# MDU_base.net
KiCad netlist of a schematic drawn in EAGLE
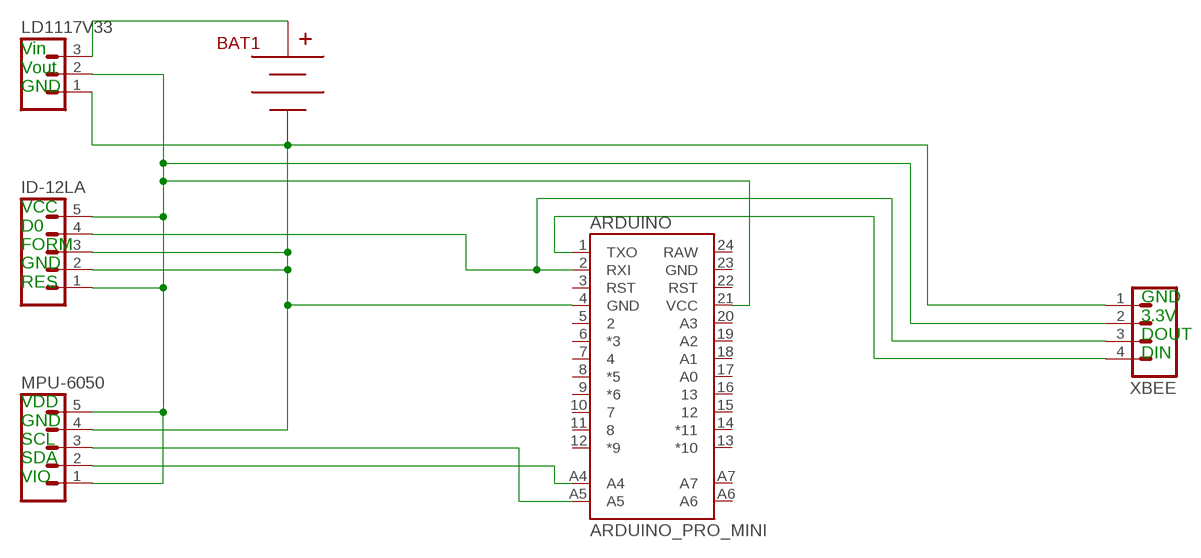
[diagram p0: schematic, sheet 1]

(export (version "E")
  (design (tool "Eeschema 10.0.6"))
  (components
    (comp (ref "ARDUINO")
      (value "ARDUINO_PRO_MINI")
      (footprint "eagle-import:ARDUINO_PRO_MINI")
      (libsource (lib "eagle-import") (part "ARDUINO_PRO_MINI"))
    )
    (comp (ref "BAT1")
      (value "BC9VPC")
      (footprint "eagle-import:BC9VPC")
      (libsource (lib "eagle-import") (part "BC9VPC"))
    )
    (comp (ref "ID-12LA")
      (value "M05NO_SILK")
      (footprint "eagle-import:1X05_NO_SILK")
      (libsource (lib "eagle-import") (part "M05NO_SILK"))
    )
    (comp (ref "LD1117V33")
      (value "M031X03_NO_SILK")
      (footprint "eagle-import:1X03_NO_SILK")
      (libsource (lib "eagle-import") (part "M031X03_NO_SILK"))
    )
    (comp (ref "MPU-6050")
      (value "M05NO_SILK")
      (footprint "eagle-import:1X05_NO_SILK")
      (libsource (lib "eagle-import") (part "M05NO_SILK"))
    )
    (comp (ref "XBEE")
      (value "M041X04_NO_SILK")
      (footprint "eagle-import:1X04_NO_SILK")
      (libsource (lib "eagle-import") (part "M041X04_NO_SILK"))
    )
  )
  (nets
    (net (code "1") (name "Net-(ARDUINO-GND-Pad4)") (class "Default")
      (node (ref "ARDUINO") (pin "4") (pinfunction "GND_4") (pintype "bidirectional"))
      (node (ref "BAT1") (pin "V-") (pinfunction "V-_V-") (pintype "bidirectional"))
      (node (ref "ID-12LA") (pin "2") (pinfunction "2_2") (pintype "passive"))
      (node (ref "ID-12LA") (pin "3") (pinfunction "3_3") (pintype "passive"))
      (node (ref "LD1117V33") (pin "1") (pinfunction "1_1") (pintype "passive"))
      (node (ref "MPU-6050") (pin "4") (pinfunction "4_4") (pintype "passive"))
      (node (ref "XBEE") (pin "1") (pinfunction "1_1") (pintype "passive"))
    )
    (net (code "2") (name "Net-(ARDUINO-PadA4)") (class "Default")
      (node (ref "ARDUINO") (pin "A4") (pinfunction "A4_A4") (pintype "bidirectional"))
      (node (ref "MPU-6050") (pin "2") (pinfunction "2_2") (pintype "passive"))
    )
    (net (code "3") (name "Net-(ARDUINO-PadA5)") (class "Default")
      (node (ref "ARDUINO") (pin "A5") (pinfunction "A5_A5") (pintype "bidirectional"))
      (node (ref "MPU-6050") (pin "3") (pinfunction "3_3") (pintype "passive"))
    )
    (net (code "4") (name "Net-(ARDUINO-RXI)") (class "Default")
      (node (ref "ARDUINO") (pin "2") (pinfunction "RXI_2") (pintype "bidirectional"))
      (node (ref "ID-12LA") (pin "4") (pinfunction "4_4") (pintype "passive"))
      (node (ref "XBEE") (pin "3") (pinfunction "3_3") (pintype "passive"))
    )
    (net (code "5") (name "Net-(ARDUINO-TXO)") (class "Default")
      (node (ref "ARDUINO") (pin "1") (pinfunction "TXO_1") (pintype "bidirectional"))
      (node (ref "XBEE") (pin "4") (pinfunction "4_4") (pintype "passive"))
    )
    (net (code "6") (name "Net-(ARDUINO-VCC)") (class "Default")
      (node (ref "ARDUINO") (pin "21") (pinfunction "VCC_21") (pintype "bidirectional"))
      (node (ref "ID-12LA") (pin "1") (pinfunction "1_1") (pintype "passive"))
      (node (ref "ID-12LA") (pin "5") (pinfunction "5_5") (pintype "passive"))
      (node (ref "LD1117V33") (pin "2") (pinfunction "2_2") (pintype "passive"))
      (node (ref "MPU-6050") (pin "1") (pinfunction "1_1") (pintype "passive"))
      (node (ref "MPU-6050") (pin "5") (pinfunction "5_5") (pintype "passive"))
      (node (ref "XBEE") (pin "2") (pinfunction "2_2") (pintype "passive"))
    )
    (net (code "7") (name "Net-(BAT1-PadV+)") (class "Default")
      (node (ref "BAT1") (pin "V+") (pinfunction "V+_V+") (pintype "bidirectional"))
      (node (ref "LD1117V33") (pin "3") (pinfunction "3_3") (pintype "passive"))
    )
    (net (code "8") (name "unconnected-(ARDUINO-*3-Pad6)") (class "Default")
      (node (ref "ARDUINO") (pin "6") (pinfunction "*3_6") (pintype "bidirectional"))
    )
    (net (code "9") (name "unconnected-(ARDUINO-*5-Pad8)") (class "Default")
      (node (ref "ARDUINO") (pin "8") (pinfunction "*5_8") (pintype "bidirectional"))
    )
    (net (code "10") (name "unconnected-(ARDUINO-*6-Pad9)") (class "Default")
      (node (ref "ARDUINO") (pin "9") (pinfunction "*6_9") (pintype "bidirectional"))
    )
    (net (code "11") (name "unconnected-(ARDUINO-*9-Pad12)") (class "Default")
      (node (ref "ARDUINO") (pin "12") (pinfunction "*9_12") (pintype "bidirectional"))
    )
    (net (code "12") (name "unconnected-(ARDUINO-*10-Pad13)") (class "Default")
      (node (ref "ARDUINO") (pin "13") (pinfunction "*10_13") (pintype "bidirectional"))
    )
    (net (code "13") (name "unconnected-(ARDUINO-*11-Pad14)") (class "Default")
      (node (ref "ARDUINO") (pin "14") (pinfunction "*11_14") (pintype "bidirectional"))
    )
    (net (code "14") (name "unconnected-(ARDUINO-2-Pad5)") (class "Default")
      (node (ref "ARDUINO") (pin "5") (pinfunction "2_5") (pintype "bidirectional"))
    )
    (net (code "15") (name "unconnected-(ARDUINO-4-Pad7)") (class "Default")
      (node (ref "ARDUINO") (pin "7") (pinfunction "4_7") (pintype "bidirectional"))
    )
    (net (code "16") (name "unconnected-(ARDUINO-7-Pad10)") (class "Default")
      (node (ref "ARDUINO") (pin "10") (pinfunction "7_10") (pintype "bidirectional"))
    )
    (net (code "17") (name "unconnected-(ARDUINO-8-Pad11)") (class "Default")
      (node (ref "ARDUINO") (pin "11") (pinfunction "8_11") (pintype "bidirectional"))
    )
    (net (code "18") (name "unconnected-(ARDUINO-12-Pad15)") (class "Default")
      (node (ref "ARDUINO") (pin "15") (pinfunction "12_15") (pintype "bidirectional"))
    )
    (net (code "19") (name "unconnected-(ARDUINO-13-Pad16)") (class "Default")
      (node (ref "ARDUINO") (pin "16") (pinfunction "13_16") (pintype "bidirectional"))
    )
    (net (code "20") (name "unconnected-(ARDUINO-A0-Pad17)") (class "Default")
      (node (ref "ARDUINO") (pin "17") (pinfunction "A0_17") (pintype "bidirectional"))
    )
    (net (code "21") (name "unconnected-(ARDUINO-A1-Pad18)") (class "Default")
      (node (ref "ARDUINO") (pin "18") (pinfunction "A1_18") (pintype "bidirectional"))
    )
    (net (code "22") (name "unconnected-(ARDUINO-A2-Pad19)") (class "Default")
      (node (ref "ARDUINO") (pin "19") (pinfunction "A2_19") (pintype "bidirectional"))
    )
    (net (code "23") (name "unconnected-(ARDUINO-A3-Pad20)") (class "Default")
      (node (ref "ARDUINO") (pin "20") (pinfunction "A3_20") (pintype "bidirectional"))
    )
    (net (code "24") (name "unconnected-(ARDUINO-GND-Pad23)") (class "Default")
      (node (ref "ARDUINO") (pin "23") (pinfunction "GND_23") (pintype "bidirectional"))
    )
    (net (code "25") (name "unconnected-(ARDUINO-PadA6)") (class "Default")
      (node (ref "ARDUINO") (pin "A6") (pinfunction "A6_A6") (pintype "bidirectional"))
    )
    (net (code "26") (name "unconnected-(ARDUINO-PadA7)") (class "Default")
      (node (ref "ARDUINO") (pin "A7") (pinfunction "A7_A7") (pintype "bidirectional"))
    )
    (net (code "27") (name "unconnected-(ARDUINO-RAW-Pad24)") (class "Default")
      (node (ref "ARDUINO") (pin "24") (pinfunction "RAW_24") (pintype "bidirectional"))
    )
    (net (code "28") (name "unconnected-(ARDUINO-RST-Pad3)") (class "Default")
      (node (ref "ARDUINO") (pin "3") (pinfunction "RST_3") (pintype "bidirectional"))
    )
    (net (code "29") (name "unconnected-(ARDUINO-RST-Pad22)") (class "Default")
      (node (ref "ARDUINO") (pin "22") (pinfunction "RST_22") (pintype "bidirectional"))
    )
  )
)
